# analog.net
KiCad netlist of a schematic drawn in EAGLE
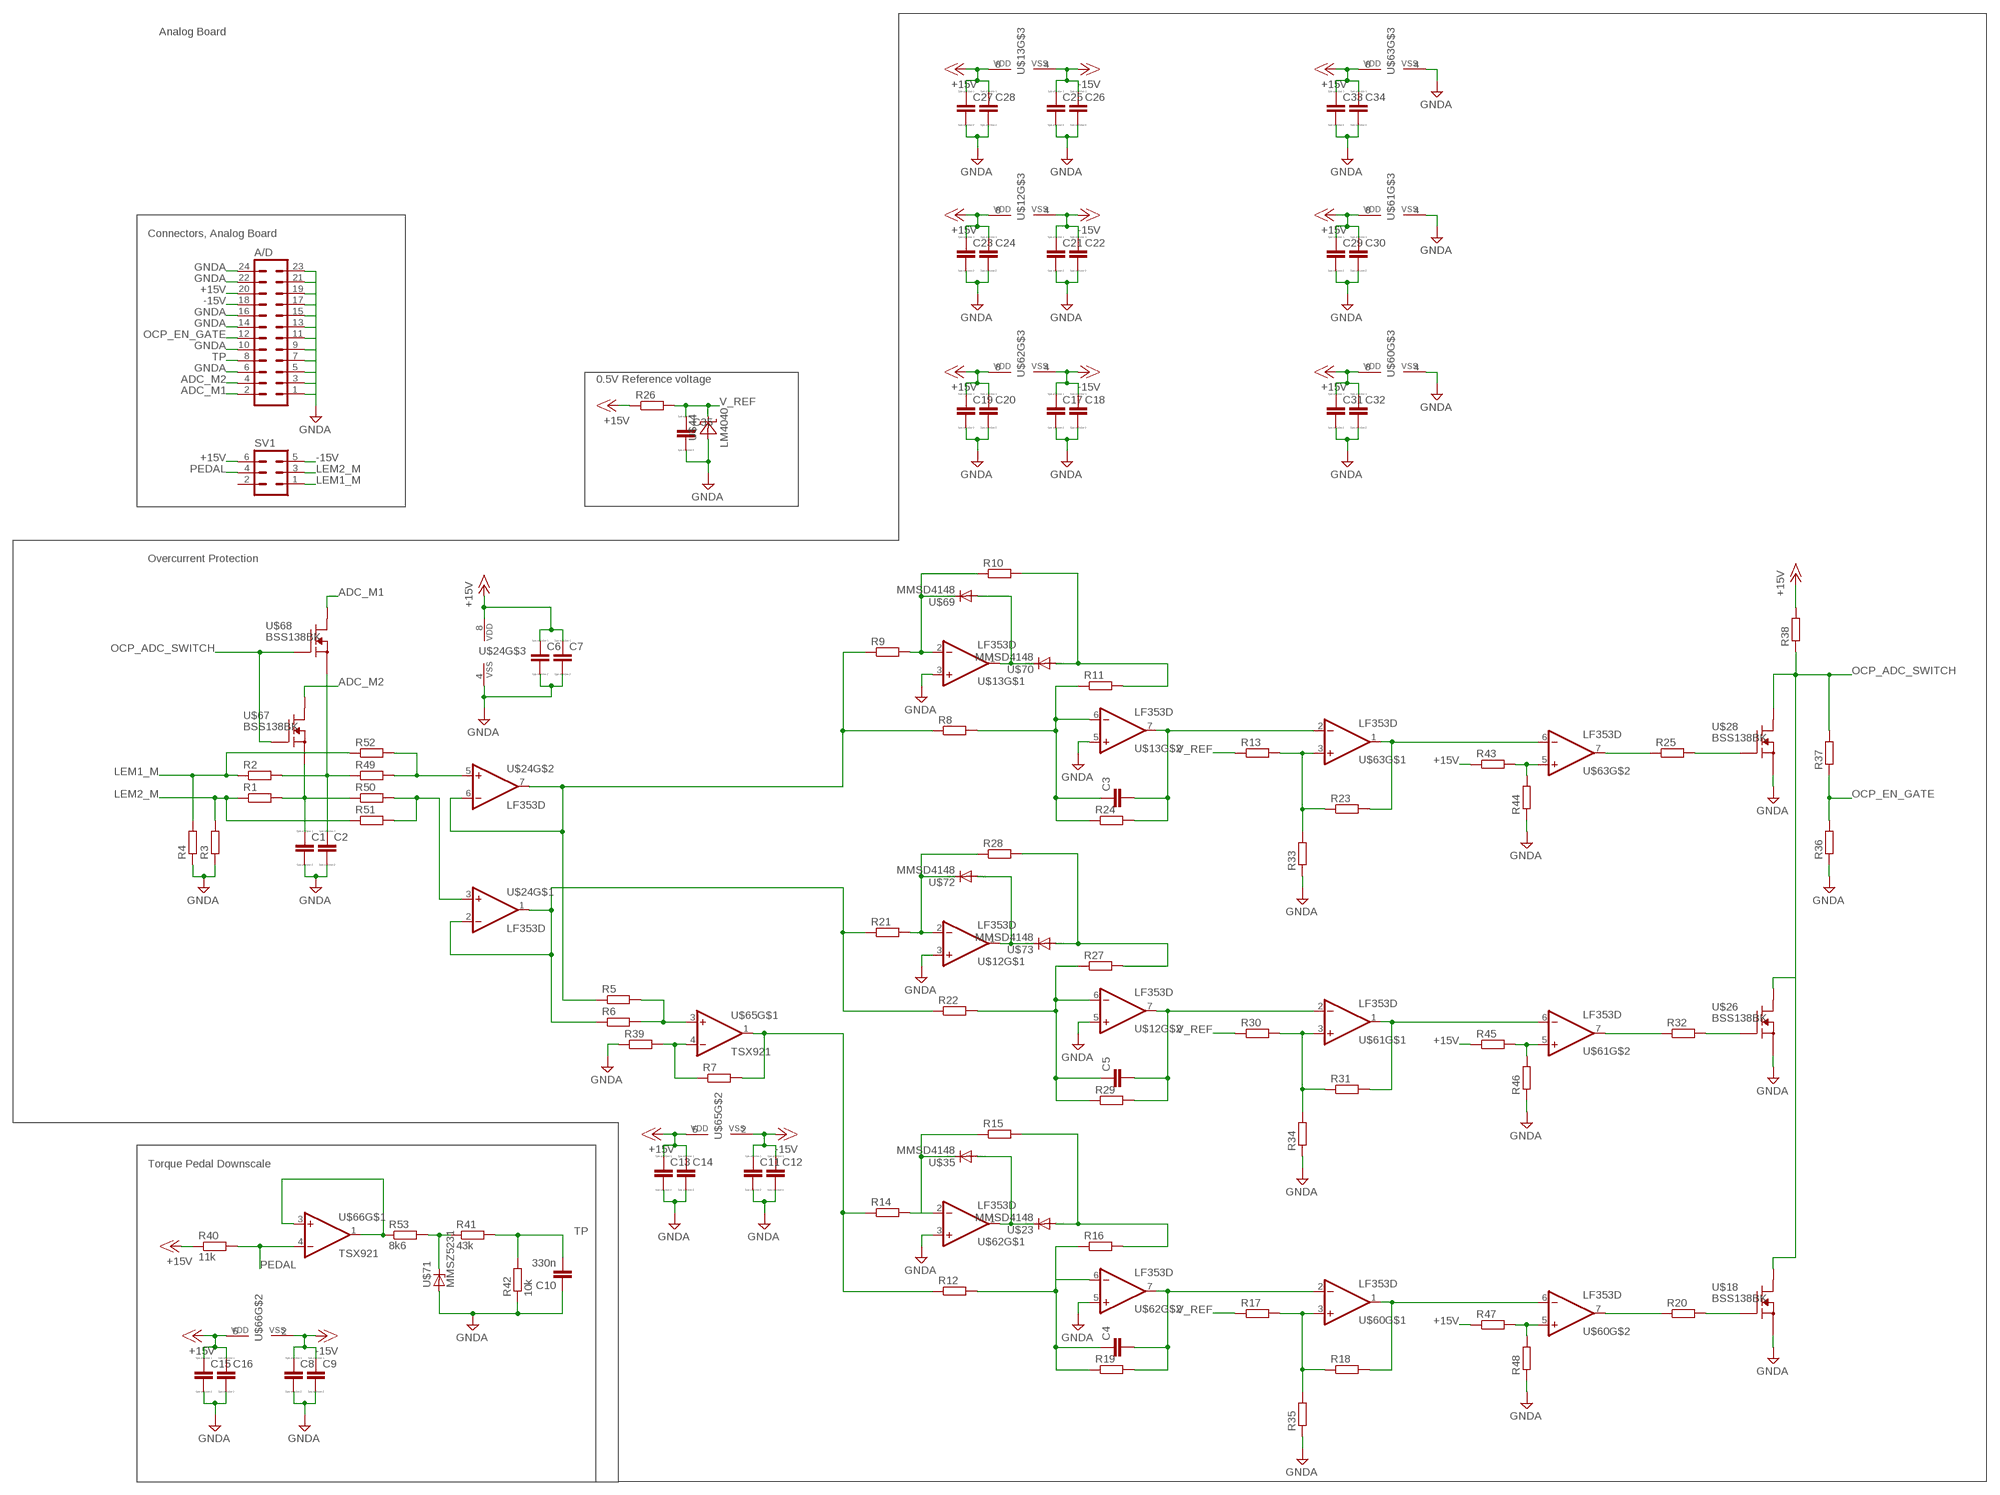
[diagram p0: schematic, sheet 1]

(export (version "E")
  (design (tool "Eeschema 10.0.6"))
  (components
    (comp (ref "A/D")
      (value "MA12-2")
      (footprint "eagle-import:MA12-2")
      (libsource (lib "eagle-import") (part "MA12-2"))
    )
    (comp (ref "C1")
      (value "CC1206")
      (footprint "eagle-import:C1206")
      (libsource (lib "eagle-import") (part "CC1206"))
    )
    (comp (ref "C2")
      (value "CC1206")
      (footprint "eagle-import:C1206")
      (libsource (lib "eagle-import") (part "CC1206"))
    )
    (comp (ref "C3")
      (value "C-EUC0805")
      (footprint "eagle-import:C0805")
      (libsource (lib "eagle-import") (part "C-EUC0805"))
    )
    (comp (ref "C4")
      (value "C-EUC0805")
      (footprint "eagle-import:C0805")
      (libsource (lib "eagle-import") (part "C-EUC0805"))
    )
    (comp (ref "C5")
      (value "C-EUC0805")
      (footprint "eagle-import:C0805")
      (libsource (lib "eagle-import") (part "C-EUC0805"))
    )
    (comp (ref "C6")
      (value "CC1206")
      (footprint "eagle-import:C1206")
      (libsource (lib "eagle-import") (part "CC1206"))
    )
    (comp (ref "C7")
      (value "CC1206")
      (footprint "eagle-import:C1206")
      (libsource (lib "eagle-import") (part "CC1206"))
    )
    (comp (ref "C8")
      (value "CC1206")
      (footprint "eagle-import:C1206")
      (libsource (lib "eagle-import") (part "CC1206"))
    )
    (comp (ref "C9")
      (value "CC1206")
      (footprint "eagle-import:C1206")
      (libsource (lib "eagle-import") (part "CC1206"))
    )
    (comp (ref "C10")
      (value "330n")
      (footprint "eagle-import:C0805")
      (libsource (lib "eagle-import") (part "C-EUC0805"))
    )
    (comp (ref "C11")
      (value "CC1206")
      (footprint "eagle-import:C1206")
      (libsource (lib "eagle-import") (part "CC1206"))
    )
    (comp (ref "C12")
      (value "CC1206")
      (footprint "eagle-import:C1206")
      (libsource (lib "eagle-import") (part "CC1206"))
    )
    (comp (ref "C13")
      (value "CC1206")
      (footprint "eagle-import:C1206")
      (libsource (lib "eagle-import") (part "CC1206"))
    )
    (comp (ref "C14")
      (value "CC1206")
      (footprint "eagle-import:C1206")
      (libsource (lib "eagle-import") (part "CC1206"))
    )
    (comp (ref "C15")
      (value "CC1206")
      (footprint "eagle-import:C1206")
      (libsource (lib "eagle-import") (part "CC1206"))
    )
    (comp (ref "C16")
      (value "CC1206")
      (footprint "eagle-import:C1206")
      (libsource (lib "eagle-import") (part "CC1206"))
    )
    (comp (ref "C17")
      (value "CC1206")
      (footprint "eagle-import:C1206")
      (libsource (lib "eagle-import") (part "CC1206"))
    )
    (comp (ref "C18")
      (value "CC1206")
      (footprint "eagle-import:C1206")
      (libsource (lib "eagle-import") (part "CC1206"))
    )
    (comp (ref "C19")
      (value "CC1206")
      (footprint "eagle-import:C1206")
      (libsource (lib "eagle-import") (part "CC1206"))
    )
    (comp (ref "C20")
      (value "CC1206")
      (footprint "eagle-import:C1206")
      (libsource (lib "eagle-import") (part "CC1206"))
    )
    (comp (ref "C21")
      (value "CC1206")
      (footprint "eagle-import:C1206")
      (libsource (lib "eagle-import") (part "CC1206"))
    )
    (comp (ref "C22")
      (value "CC1206")
      (footprint "eagle-import:C1206")
      (libsource (lib "eagle-import") (part "CC1206"))
    )
    (comp (ref "C23")
      (value "CC1206")
      (footprint "eagle-import:C1206")
      (libsource (lib "eagle-import") (part "CC1206"))
    )
    (comp (ref "C24")
      (value "CC1206")
      (footprint "eagle-import:C1206")
      (libsource (lib "eagle-import") (part "CC1206"))
    )
    (comp (ref "C25")
      (value "CC1206")
      (footprint "eagle-import:C1206")
      (libsource (lib "eagle-import") (part "CC1206"))
    )
    (comp (ref "C26")
      (value "CC1206")
      (footprint "eagle-import:C1206")
      (libsource (lib "eagle-import") (part "CC1206"))
    )
    (comp (ref "C27")
      (value "CC1206")
      (footprint "eagle-import:C1206")
      (libsource (lib "eagle-import") (part "CC1206"))
    )
    (comp (ref "C28")
      (value "CC1206")
      (footprint "eagle-import:C1206")
      (libsource (lib "eagle-import") (part "CC1206"))
    )
    (comp (ref "C29")
      (value "CC1206")
      (footprint "eagle-import:C1206")
      (libsource (lib "eagle-import") (part "CC1206"))
    )
    (comp (ref "C30")
      (value "CC1206")
      (footprint "eagle-import:C1206")
      (libsource (lib "eagle-import") (part "CC1206"))
    )
    (comp (ref "C31")
      (value "CC1206")
      (footprint "eagle-import:C1206")
      (libsource (lib "eagle-import") (part "CC1206"))
    )
    (comp (ref "C32")
      (value "CC1206")
      (footprint "eagle-import:C1206")
      (libsource (lib "eagle-import") (part "CC1206"))
    )
    (comp (ref "C33")
      (value "CC1206")
      (footprint "eagle-import:C1206")
      (libsource (lib "eagle-import") (part "CC1206"))
    )
    (comp (ref "C34")
      (value "CC1206")
      (footprint "eagle-import:C1206")
      (libsource (lib "eagle-import") (part "CC1206"))
    )
    (comp (ref "C35")
      (value "CC1206")
      (footprint "eagle-import:C1206")
      (libsource (lib "eagle-import") (part "CC1206"))
    )
    (comp (ref "R1")
      (value "R-EU_M0805")
      (footprint "eagle-import:M0805")
      (libsource (lib "eagle-import") (part "R-EU_M0805"))
    )
    (comp (ref "R2")
      (value "R-EU_M0805")
      (footprint "eagle-import:M0805")
      (libsource (lib "eagle-import") (part "R-EU_M0805"))
    )
    (comp (ref "R3")
      (value "R-EU_M0805")
      (footprint "eagle-import:M0805")
      (libsource (lib "eagle-import") (part "R-EU_M0805"))
    )
    (comp (ref "R4")
      (value "R-EU_M0805")
      (footprint "eagle-import:M0805")
      (libsource (lib "eagle-import") (part "R-EU_M0805"))
    )
    (comp (ref "R5")
      (value "R-EU_M0805")
      (footprint "eagle-import:M0805")
      (libsource (lib "eagle-import") (part "R-EU_M0805"))
    )
    (comp (ref "R6")
      (value "R-EU_M0805")
      (footprint "eagle-import:M0805")
      (libsource (lib "eagle-import") (part "R-EU_M0805"))
    )
    (comp (ref "R7")
      (value "R-EU_M0805")
      (footprint "eagle-import:M0805")
      (libsource (lib "eagle-import") (part "R-EU_M0805"))
    )
    (comp (ref "R8")
      (value "R-EU_M0805")
      (footprint "eagle-import:M0805")
      (libsource (lib "eagle-import") (part "R-EU_M0805"))
    )
    (comp (ref "R9")
      (value "R-EU_M0805")
      (footprint "eagle-import:M0805")
      (libsource (lib "eagle-import") (part "R-EU_M0805"))
    )
    (comp (ref "R10")
      (value "R-EU_M0805")
      (footprint "eagle-import:M0805")
      (libsource (lib "eagle-import") (part "R-EU_M0805"))
    )
    (comp (ref "R11")
      (value "R-EU_M0805")
      (footprint "eagle-import:M0805")
      (libsource (lib "eagle-import") (part "R-EU_M0805"))
    )
    (comp (ref "R12")
      (value "R-EU_M0805")
      (footprint "eagle-import:M0805")
      (libsource (lib "eagle-import") (part "R-EU_M0805"))
    )
    (comp (ref "R13")
      (value "R-EU_M0805")
      (footprint "eagle-import:M0805")
      (libsource (lib "eagle-import") (part "R-EU_M0805"))
    )
    (comp (ref "R14")
      (value "R-EU_M0805")
      (footprint "eagle-import:M0805")
      (libsource (lib "eagle-import") (part "R-EU_M0805"))
    )
    (comp (ref "R15")
      (value "R-EU_M0805")
      (footprint "eagle-import:M0805")
      (libsource (lib "eagle-import") (part "R-EU_M0805"))
    )
    (comp (ref "R16")
      (value "R-EU_M0805")
      (footprint "eagle-import:M0805")
      (libsource (lib "eagle-import") (part "R-EU_M0805"))
    )
    (comp (ref "R17")
      (value "R-EU_M0805")
      (footprint "eagle-import:M0805")
      (libsource (lib "eagle-import") (part "R-EU_M0805"))
    )
    (comp (ref "R18")
      (value "R-EU_M0805")
      (footprint "eagle-import:M0805")
      (libsource (lib "eagle-import") (part "R-EU_M0805"))
    )
    (comp (ref "R19")
      (value "R-EU_M0805")
      (footprint "eagle-import:M0805")
      (libsource (lib "eagle-import") (part "R-EU_M0805"))
    )
    (comp (ref "R20")
      (value "R-EU_M0805")
      (footprint "eagle-import:M0805")
      (libsource (lib "eagle-import") (part "R-EU_M0805"))
    )
    (comp (ref "R21")
      (value "R-EU_M0805")
      (footprint "eagle-import:M0805")
      (libsource (lib "eagle-import") (part "R-EU_M0805"))
    )
    (comp (ref "R22")
      (value "R-EU_M0805")
      (footprint "eagle-import:M0805")
      (libsource (lib "eagle-import") (part "R-EU_M0805"))
    )
    (comp (ref "R23")
      (value "R-EU_M0805")
      (footprint "eagle-import:M0805")
      (libsource (lib "eagle-import") (part "R-EU_M0805"))
    )
    (comp (ref "R24")
      (value "R-EU_M0805")
      (footprint "eagle-import:M0805")
      (libsource (lib "eagle-import") (part "R-EU_M0805"))
    )
    (comp (ref "R25")
      (value "R-EU_M0805")
      (footprint "eagle-import:M0805")
      (libsource (lib "eagle-import") (part "R-EU_M0805"))
    )
    (comp (ref "R26")
      (value "R-EU_M0805")
      (footprint "eagle-import:M0805")
      (libsource (lib "eagle-import") (part "R-EU_M0805"))
    )
    (comp (ref "R27")
      (value "R-EU_M0805")
      (footprint "eagle-import:M0805")
      (libsource (lib "eagle-import") (part "R-EU_M0805"))
    )
    (comp (ref "R28")
      (value "R-EU_M0805")
      (footprint "eagle-import:M0805")
      (libsource (lib "eagle-import") (part "R-EU_M0805"))
    )
    (comp (ref "R29")
      (value "R-EU_M0805")
      (footprint "eagle-import:M0805")
      (libsource (lib "eagle-import") (part "R-EU_M0805"))
    )
    (comp (ref "R30")
      (value "R-EU_M0805")
      (footprint "eagle-import:M0805")
      (libsource (lib "eagle-import") (part "R-EU_M0805"))
    )
    (comp (ref "R31")
      (value "R-EU_M0805")
      (footprint "eagle-import:M0805")
      (libsource (lib "eagle-import") (part "R-EU_M0805"))
    )
    (comp (ref "R32")
      (value "R-EU_M0805")
      (footprint "eagle-import:M0805")
      (libsource (lib "eagle-import") (part "R-EU_M0805"))
    )
    (comp (ref "R33")
      (value "R-EU_M0805")
      (footprint "eagle-import:M0805")
      (libsource (lib "eagle-import") (part "R-EU_M0805"))
    )
    (comp (ref "R34")
      (value "R-EU_M0805")
      (footprint "eagle-import:M0805")
      (libsource (lib "eagle-import") (part "R-EU_M0805"))
    )
    (comp (ref "R35")
      (value "R-EU_M0805")
      (footprint "eagle-import:M0805")
      (libsource (lib "eagle-import") (part "R-EU_M0805"))
    )
    (comp (ref "R36")
      (value "R-EU_M0805")
      (footprint "eagle-import:M0805")
      (libsource (lib "eagle-import") (part "R-EU_M0805"))
    )
    (comp (ref "R37")
      (value "R-EU_M0805")
      (footprint "eagle-import:M0805")
      (libsource (lib "eagle-import") (part "R-EU_M0805"))
    )
    (comp (ref "R38")
      (value "R-EU_M0805")
      (footprint "eagle-import:M0805")
      (libsource (lib "eagle-import") (part "R-EU_M0805"))
    )
    (comp (ref "R39")
      (value "R-EU_M0805")
      (footprint "eagle-import:M0805")
      (libsource (lib "eagle-import") (part "R-EU_M0805"))
    )
    (comp (ref "R40")
      (value "11k")
      (footprint "eagle-import:M0805")
      (libsource (lib "eagle-import") (part "R-EU_M0805"))
    )
    (comp (ref "R41")
      (value "43k")
      (footprint "eagle-import:M0805")
      (libsource (lib "eagle-import") (part "R-EU_M0805"))
    )
    (comp (ref "R42")
      (value "10k")
      (footprint "eagle-import:M0805")
      (libsource (lib "eagle-import") (part "R-EU_M0805"))
    )
    (comp (ref "R43")
      (value "R-EU_M0805")
      (footprint "eagle-import:M0805")
      (libsource (lib "eagle-import") (part "R-EU_M0805"))
    )
    (comp (ref "R44")
      (value "R-EU_M0805")
      (footprint "eagle-import:M0805")
      (libsource (lib "eagle-import") (part "R-EU_M0805"))
    )
    (comp (ref "R45")
      (value "R-EU_M0805")
      (footprint "eagle-import:M0805")
      (libsource (lib "eagle-import") (part "R-EU_M0805"))
    )
    (comp (ref "R46")
      (value "R-EU_M0805")
      (footprint "eagle-import:M0805")
      (libsource (lib "eagle-import") (part "R-EU_M0805"))
    )
    (comp (ref "R47")
      (value "R-EU_M0805")
      (footprint "eagle-import:M0805")
      (libsource (lib "eagle-import") (part "R-EU_M0805"))
    )
    (comp (ref "R48")
      (value "R-EU_M0805")
      (footprint "eagle-import:M0805")
      (libsource (lib "eagle-import") (part "R-EU_M0805"))
    )
    (comp (ref "R49")
      (value "R-EU_M0805")
      (footprint "eagle-import:M0805")
      (libsource (lib "eagle-import") (part "R-EU_M0805"))
    )
    (comp (ref "R50")
      (value "R-EU_M0805")
      (footprint "eagle-import:M0805")
      (libsource (lib "eagle-import") (part "R-EU_M0805"))
    )
    (comp (ref "R51")
      (value "R-EU_M0805")
      (footprint "eagle-import:M0805")
      (libsource (lib "eagle-import") (part "R-EU_M0805"))
    )
    (comp (ref "R52")
      (value "R-EU_M0805")
      (footprint "eagle-import:M0805")
      (libsource (lib "eagle-import") (part "R-EU_M0805"))
    )
    (comp (ref "R53")
      (value "8k6")
      (footprint "eagle-import:M0805")
      (libsource (lib "eagle-import") (part "R-EU_M0805"))
    )
    (comp (ref "SV1")
      (value "MA03-2")
      (footprint "eagle-import:MA03-2")
      (libsource (lib "eagle-import") (part "MA03-2"))
    )
    (comp (ref "U$12")
      (value "LF353D")
      (footprint "eagle-import:SO08")
      (libsource (lib "eagle-import") (part "LF353D"))
    )
    (comp (ref "U$13")
      (value "LF353D")
      (footprint "eagle-import:SO08")
      (libsource (lib "eagle-import") (part "LF353D"))
    )
    (comp (ref "U$18")
      (value "BSS138BK")
      (footprint "eagle-import:SOT23")
      (libsource (lib "eagle-import") (part "BSS138BK"))
    )
    (comp (ref "U$23")
      (value "MMSD4148")
      (footprint "eagle-import:SOD123")
      (libsource (lib "eagle-import") (part "MMSD4148"))
    )
    (comp (ref "U$24")
      (value "LF353D")
      (footprint "eagle-import:SO08")
      (libsource (lib "eagle-import") (part "LF353D"))
    )
    (comp (ref "U$26")
      (value "BSS138BK")
      (footprint "eagle-import:SOT23")
      (libsource (lib "eagle-import") (part "BSS138BK"))
    )
    (comp (ref "U$28")
      (value "BSS138BK")
      (footprint "eagle-import:SOT23")
      (libsource (lib "eagle-import") (part "BSS138BK"))
    )
    (comp (ref "U$35")
      (value "MMSD4148")
      (footprint "eagle-import:SOD123")
      (libsource (lib "eagle-import") (part "MMSD4148"))
    )
    (comp (ref "U$44")
      (value "LM4040")
      (footprint "eagle-import:SOT23")
      (libsource (lib "eagle-import") (part "LM4040"))
    )
    (comp (ref "U$60")
      (value "LF353D")
      (footprint "eagle-import:SO08")
      (libsource (lib "eagle-import") (part "LF353D"))
    )
    (comp (ref "U$61")
      (value "LF353D")
      (footprint "eagle-import:SO08")
      (libsource (lib "eagle-import") (part "LF353D"))
    )
    (comp (ref "U$62")
      (value "LF353D")
      (footprint "eagle-import:SO08")
      (libsource (lib "eagle-import") (part "LF353D"))
    )
    (comp (ref "U$63")
      (value "LF353D")
      (footprint "eagle-import:SO08")
      (libsource (lib "eagle-import") (part "LF353D"))
    )
    (comp (ref "U$65")
      (value "TSX921")
      (footprint "eagle-import:SOT23-5")
      (libsource (lib "eagle-import") (part "TSX921"))
    )
    (comp (ref "U$66")
      (value "TSX921")
      (footprint "eagle-import:SOT23-5")
      (libsource (lib "eagle-import") (part "TSX921"))
    )
    (comp (ref "U$67")
      (value "BSS138BK")
      (footprint "eagle-import:SOT23")
      (libsource (lib "eagle-import") (part "BSS138BK"))
    )
    (comp (ref "U$68")
      (value "BSS138BK")
      (footprint "eagle-import:SOT23")
      (libsource (lib "eagle-import") (part "BSS138BK"))
    )
    (comp (ref "U$69")
      (value "MMSD4148")
      (footprint "eagle-import:SOD123")
      (libsource (lib "eagle-import") (part "MMSD4148"))
    )
    (comp (ref "U$70")
      (value "MMSD4148")
      (footprint "eagle-import:SOD123")
      (libsource (lib "eagle-import") (part "MMSD4148"))
    )
    (comp (ref "U$71")
      (value "MMSZ5231")
      (footprint "eagle-import:SOD123")
      (libsource (lib "eagle-import") (part "MMSZ5231"))
    )
    (comp (ref "U$72")
      (value "MMSD4148")
      (footprint "eagle-import:SOD123")
      (libsource (lib "eagle-import") (part "MMSD4148"))
    )
    (comp (ref "U$73")
      (value "MMSD4148")
      (footprint "eagle-import:SOD123")
      (libsource (lib "eagle-import") (part "MMSD4148"))
    )
  )
  (nets
    (net (code "1") (name "+15V") (class "Default")
      (node (ref "A/D") (pin "20") (pinfunction "20_20") (pintype "passive"))
      (node (ref "C13") (pin "1") (pinfunction "1_1") (pintype "passive"))
      (node (ref "C14") (pin "1") (pinfunction "1_1") (pintype "passive"))
      (node (ref "C15") (pin "1") (pinfunction "1_1") (pintype "passive"))
      (node (ref "C16") (pin "1") (pinfunction "1_1") (pintype "passive"))
      (node (ref "C19") (pin "1") (pinfunction "1_1") (pintype "passive"))
      (node (ref "C20") (pin "1") (pinfunction "1_1") (pintype "passive"))
      (node (ref "C23") (pin "1") (pinfunction "1_1") (pintype "passive"))
      (node (ref "C24") (pin "1") (pinfunction "1_1") (pintype "passive"))
      (node (ref "C27") (pin "1") (pinfunction "1_1") (pintype "passive"))
      (node (ref "C28") (pin "1") (pinfunction "1_1") (pintype "passive"))
      (node (ref "C29") (pin "1") (pinfunction "1_1") (pintype "passive"))
      (node (ref "C30") (pin "1") (pinfunction "1_1") (pintype "passive"))
      (node (ref "C31") (pin "1") (pinfunction "1_1") (pintype "passive"))
      (node (ref "C32") (pin "1") (pinfunction "1_1") (pintype "passive"))
      (node (ref "C33") (pin "1") (pinfunction "1_1") (pintype "passive"))
      (node (ref "C34") (pin "1") (pinfunction "1_1") (pintype "passive"))
      (node (ref "C6") (pin "1") (pinfunction "1_1") (pintype "passive"))
      (node (ref "C7") (pin "1") (pinfunction "1_1") (pintype "passive"))
      (node (ref "R26") (pin "1") (pinfunction "1_1") (pintype "passive"))
      (node (ref "R38") (pin "2") (pinfunction "2_2") (pintype "passive"))
      (node (ref "R40") (pin "1") (pinfunction "1_1") (pintype "passive"))
      (node (ref "R43") (pin "1") (pinfunction "1_1") (pintype "passive"))
      (node (ref "R45") (pin "1") (pinfunction "1_1") (pintype "passive"))
      (node (ref "R47") (pin "1") (pinfunction "1_1") (pintype "passive"))
      (node (ref "SV1") (pin "6") (pinfunction "6_6") (pintype "passive"))
      (node (ref "U$12") (pin "8") (pinfunction "VDD_8") (pintype "power_in"))
      (node (ref "U$13") (pin "8") (pinfunction "VDD_8") (pintype "power_in"))
      (node (ref "U$24") (pin "8") (pinfunction "VDD_8") (pintype "power_in"))
      (node (ref "U$60") (pin "8") (pinfunction "VDD_8") (pintype "power_in"))
      (node (ref "U$61") (pin "8") (pinfunction "VDD_8") (pintype "power_in"))
      (node (ref "U$62") (pin "8") (pinfunction "VDD_8") (pintype "power_in"))
      (node (ref "U$63") (pin "8") (pinfunction "VDD_8") (pintype "power_in"))
      (node (ref "U$65") (pin "5") (pinfunction "VDD_5") (pintype "power_in"))
      (node (ref "U$66") (pin "5") (pinfunction "VDD_5") (pintype "power_in"))
    )
    (net (code "2") (name "-15V") (class "Default")
      (node (ref "A/D") (pin "18") (pinfunction "18_18") (pintype "passive"))
      (node (ref "C11") (pin "1") (pinfunction "1_1") (pintype "passive"))
      (node (ref "C12") (pin "1") (pinfunction "1_1") (pintype "passive"))
      (node (ref "C17") (pin "1") (pinfunction "1_1") (pintype "passive"))
      (node (ref "C18") (pin "1") (pinfunction "1_1") (pintype "passive"))
      (node (ref "C21") (pin "1") (pinfunction "1_1") (pintype "passive"))
      (node (ref "C22") (pin "1") (pinfunction "1_1") (pintype "passive"))
      (node (ref "C25") (pin "1") (pinfunction "1_1") (pintype "passive"))
      (node (ref "C26") (pin "1") (pinfunction "1_1") (pintype "passive"))
      (node (ref "C8") (pin "1") (pinfunction "1_1") (pintype "passive"))
      (node (ref "C9") (pin "1") (pinfunction "1_1") (pintype "passive"))
      (node (ref "SV1") (pin "5") (pinfunction "5_5") (pintype "passive"))
      (node (ref "U$12") (pin "4") (pinfunction "VSS_4") (pintype "power_in"))
      (node (ref "U$13") (pin "4") (pinfunction "VSS_4") (pintype "power_in"))
      (node (ref "U$62") (pin "4") (pinfunction "VSS_4") (pintype "power_in"))
      (node (ref "U$65") (pin "2") (pinfunction "VSS_2") (pintype "power_in"))
      (node (ref "U$66") (pin "2") (pinfunction "VSS_2") (pintype "power_in"))
    )
    (net (code "3") (name "/ADC_M1") (class "Default")
      (node (ref "A/D") (pin "2") (pinfunction "2_2") (pintype "passive"))
      (node (ref "U$68") (pin "3") (pinfunction "D_3") (pintype "passive"))
    )
    (net (code "4") (name "/ADC_M2") (class "Default")
      (node (ref "A/D") (pin "4") (pinfunction "4_4") (pintype "passive"))
      (node (ref "U$67") (pin "3") (pinfunction "D_3") (pintype "passive"))
    )
    (net (code "5") (name "/LEM1_M") (class "Default")
      (node (ref "R2") (pin "1") (pinfunction "1_1") (pintype "passive"))
      (node (ref "R4") (pin "2") (pinfunction "2_2") (pintype "passive"))
      (node (ref "R52") (pin "1") (pinfunction "1_1") (pintype "passive"))
      (node (ref "SV1") (pin "1") (pinfunction "1_1") (pintype "passive"))
    )
    (net (code "6") (name "/LEM2_M") (class "Default")
      (node (ref "R1") (pin "1") (pinfunction "1_1") (pintype "passive"))
      (node (ref "R3") (pin "2") (pinfunction "2_2") (pintype "passive"))
      (node (ref "R51") (pin "1") (pinfunction "1_1") (pintype "passive"))
      (node (ref "SV1") (pin "3") (pinfunction "3_3") (pintype "passive"))
    )
    (net (code "7") (name "/OCP_ADC_SWITCH") (class "Default")
      (node (ref "R37") (pin "2") (pinfunction "2_2") (pintype "passive"))
      (node (ref "R38") (pin "1") (pinfunction "1_1") (pintype "passive"))
      (node (ref "U$18") (pin "3") (pinfunction "D_3") (pintype "passive"))
      (node (ref "U$26") (pin "3") (pinfunction "D_3") (pintype "passive"))
      (node (ref "U$28") (pin "3") (pinfunction "D_3") (pintype "passive"))
      (node (ref "U$67") (pin "1") (pinfunction "G_1") (pintype "passive"))
      (node (ref "U$68") (pin "1") (pinfunction "G_1") (pintype "passive"))
    )
    (net (code "8") (name "/OCP_EN_GATE") (class "Default")
      (node (ref "A/D") (pin "12") (pinfunction "12_12") (pintype "passive"))
      (node (ref "R36") (pin "2") (pinfunction "2_2") (pintype "passive"))
      (node (ref "R37") (pin "1") (pinfunction "1_1") (pintype "passive"))
    )
    (net (code "9") (name "/PEDAL") (class "Default")
      (node (ref "R40") (pin "2") (pinfunction "2_2") (pintype "passive"))
      (node (ref "SV1") (pin "4") (pinfunction "4_4") (pintype "passive"))
      (node (ref "U$66") (pin "4") (pinfunction "-IN_4") (pintype "input"))
    )
    (net (code "10") (name "/TP") (class "Default")
      (node (ref "A/D") (pin "8") (pinfunction "8_8") (pintype "passive"))
      (node (ref "C10") (pin "2") (pinfunction "2_2") (pintype "passive"))
      (node (ref "R41") (pin "2") (pinfunction "2_2") (pintype "passive"))
      (node (ref "R42") (pin "2") (pinfunction "2_2") (pintype "passive"))
    )
    (net (code "11") (name "/V_REF") (class "Default")
      (node (ref "C35") (pin "1") (pinfunction "1_1") (pintype "passive"))
      (node (ref "R13") (pin "1") (pinfunction "1_1") (pintype "passive"))
      (node (ref "R17") (pin "1") (pinfunction "1_1") (pintype "passive"))
      (node (ref "R26") (pin "2") (pinfunction "2_2") (pintype "passive"))
      (node (ref "R30") (pin "1") (pinfunction "1_1") (pintype "passive"))
      (node (ref "U$44") (pin "2") (pinfunction "C_2") (pintype "passive"))
    )
    (net (code "12") (name "GNDA") (class "Default")
      (node (ref "A/D") (pin "1") (pinfunction "1_1") (pintype "passive"))
      (node (ref "A/D") (pin "10") (pinfunction "10_10") (pintype "passive"))
      (node (ref "A/D") (pin "11") (pinfunction "11_11") (pintype "passive"))
      (node (ref "A/D") (pin "13") (pinfunction "13_13") (pintype "passive"))
      (node (ref "A/D") (pin "14") (pinfunction "14_14") (pintype "passive"))
      (node (ref "A/D") (pin "15") (pinfunction "15_15") (pintype "passive"))
      (node (ref "A/D") (pin "16") (pinfunction "16_16") (pintype "passive"))
      (node (ref "A/D") (pin "22") (pinfunction "22_22") (pintype "passive"))
      (node (ref "A/D") (pin "23") (pinfunction "23_23") (pintype "passive"))
      (node (ref "A/D") (pin "24") (pinfunction "24_24") (pintype "passive"))
      (node (ref "A/D") (pin "3") (pinfunction "3_3") (pintype "passive"))
      (node (ref "A/D") (pin "5") (pinfunction "5_5") (pintype "passive"))
      (node (ref "A/D") (pin "6") (pinfunction "6_6") (pintype "passive"))
      (node (ref "A/D") (pin "7") (pinfunction "7_7") (pintype "passive"))
      (node (ref "A/D") (pin "9") (pinfunction "9_9") (pintype "passive"))
      (node (ref "C1") (pin "2") (pinfunction "2_2") (pintype "passive"))
      (node (ref "C10") (pin "1") (pinfunction "1_1") (pintype "passive"))
      (node (ref "C11") (pin "2") (pinfunction "2_2") (pintype "passive"))
      (node (ref "C12") (pin "2") (pinfunction "2_2") (pintype "passive"))
      (node (ref "C13") (pin "2") (pinfunction "2_2") (pintype "passive"))
      (node (ref "C14") (pin "2") (pinfunction "2_2") (pintype "passive"))
      (node (ref "C15") (pin "2") (pinfunction "2_2") (pintype "passive"))
      (node (ref "C16") (pin "2") (pinfunction "2_2") (pintype "passive"))
      (node (ref "C17") (pin "2") (pinfunction "2_2") (pintype "passive"))
      (node (ref "C18") (pin "2") (pinfunction "2_2") (pintype "passive"))
      (node (ref "C19") (pin "2") (pinfunction "2_2") (pintype "passive"))
      (node (ref "C2") (pin "2") (pinfunction "2_2") (pintype "passive"))
      (node (ref "C20") (pin "2") (pinfunction "2_2") (pintype "passive"))
      (node (ref "C21") (pin "2") (pinfunction "2_2") (pintype "passive"))
      (node (ref "C22") (pin "2") (pinfunction "2_2") (pintype "passive"))
      (node (ref "C23") (pin "2") (pinfunction "2_2") (pintype "passive"))
      (node (ref "C24") (pin "2") (pinfunction "2_2") (pintype "passive"))
      (node (ref "C25") (pin "2") (pinfunction "2_2") (pintype "passive"))
      (node (ref "C26") (pin "2") (pinfunction "2_2") (pintype "passive"))
      (node (ref "C27") (pin "2") (pinfunction "2_2") (pintype "passive"))
      (node (ref "C28") (pin "2") (pinfunction "2_2") (pintype "passive"))
      (node (ref "C29") (pin "2") (pinfunction "2_2") (pintype "passive"))
      (node (ref "C30") (pin "2") (pinfunction "2_2") (pintype "passive"))
      (node (ref "C31") (pin "2") (pinfunction "2_2") (pintype "passive"))
      (node (ref "C32") (pin "2") (pinfunction "2_2") (pintype "passive"))
      (node (ref "C33") (pin "2") (pinfunction "2_2") (pintype "passive"))
      (node (ref "C34") (pin "2") (pinfunction "2_2") (pintype "passive"))
      (node (ref "C35") (pin "2") (pinfunction "2_2") (pintype "passive"))
      (node (ref "C6") (pin "2") (pinfunction "2_2") (pintype "passive"))
      (node (ref "C7") (pin "2") (pinfunction "2_2") (pintype "passive"))
      (node (ref "C8") (pin "2") (pinfunction "2_2") (pintype "passive"))
      (node (ref "C9") (pin "2") (pinfunction "2_2") (pintype "passive"))
      (node (ref "R3") (pin "1") (pinfunction "1_1") (pintype "passive"))
      (node (ref "R33") (pin "1") (pinfunction "1_1") (pintype "passive"))
      (node (ref "R34") (pin "1") (pinfunction "1_1") (pintype "passive"))
      (node (ref "R35") (pin "1") (pinfunction "1_1") (pintype "passive"))
      (node (ref "R36") (pin "1") (pinfunction "1_1") (pintype "passive"))
      (node (ref "R39") (pin "1") (pinfunction "1_1") (pintype "passive"))
      (node (ref "R4") (pin "1") (pinfunction "1_1") (pintype "passive"))
      (node (ref "R42") (pin "1") (pinfunction "1_1") (pintype "passive"))
      (node (ref "R44") (pin "1") (pinfunction "1_1") (pintype "passive"))
      (node (ref "R46") (pin "1") (pinfunction "1_1") (pintype "passive"))
      (node (ref "R48") (pin "1") (pinfunction "1_1") (pintype "passive"))
      (node (ref "U$12") (pin "3") (pinfunction "+IN_3") (pintype "input"))
      (node (ref "U$12") (pin "5") (pinfunction "+IN_5") (pintype "input"))
      (node (ref "U$13") (pin "3") (pinfunction "+IN_3") (pintype "input"))
      (node (ref "U$13") (pin "5") (pinfunction "+IN_5") (pintype "input"))
      (node (ref "U$18") (pin "2") (pinfunction "S_2") (pintype "passive"))
      (node (ref "U$24") (pin "4") (pinfunction "VSS_4") (pintype "power_in"))
      (node (ref "U$26") (pin "2") (pinfunction "S_2") (pintype "passive"))
      (node (ref "U$28") (pin "2") (pinfunction "S_2") (pintype "passive"))
      (node (ref "U$44") (pin "1") (pinfunction "A_1") (pintype "passive"))
      (node (ref "U$60") (pin "4") (pinfunction "VSS_4") (pintype "power_in"))
      (node (ref "U$61") (pin "4") (pinfunction "VSS_4") (pintype "power_in"))
      (node (ref "U$62") (pin "3") (pinfunction "+IN_3") (pintype "input"))
      (node (ref "U$62") (pin "5") (pinfunction "+IN_5") (pintype "input"))
      (node (ref "U$63") (pin "4") (pinfunction "VSS_4") (pintype "power_in"))
      (node (ref "U$71") (pin "A") (pinfunction "A_A") (pintype "passive"))
    )
    (net (code "13") (name "Net-(R10-Pad2)") (class "Default")
      (node (ref "R10") (pin "2") (pinfunction "2_2") (pintype "passive"))
      (node (ref "R11") (pin "2") (pinfunction "2_2") (pintype "passive"))
      (node (ref "U$70") (pin "A") (pinfunction "A_A") (pintype "passive"))
    )
    (net (code "14") (name "Net-(R15-Pad2)") (class "Default")
      (node (ref "R15") (pin "2") (pinfunction "2_2") (pintype "passive"))
      (node (ref "R16") (pin "2") (pinfunction "2_2") (pintype "passive"))
      (node (ref "U$23") (pin "A") (pinfunction "A_A") (pintype "passive"))
    )
    (net (code "15") (name "Net-(R27-Pad2)") (class "Default")
      (node (ref "R27") (pin "2") (pinfunction "2_2") (pintype "passive"))
      (node (ref "R28") (pin "2") (pinfunction "2_2") (pintype "passive"))
      (node (ref "U$73") (pin "A") (pinfunction "A_A") (pintype "passive"))
    )
    (net (code "16") (name "Net-(R41-Pad1)") (class "Default")
      (node (ref "R41") (pin "1") (pinfunction "1_1") (pintype "passive"))
      (node (ref "R53") (pin "2") (pinfunction "2_2") (pintype "passive"))
      (node (ref "U$71") (pin "C") (pinfunction "C_C") (pintype "passive"))
    )
    (net (code "17") (name "Net-(U$12A--IN)") (class "Default")
      (node (ref "R21") (pin "2") (pinfunction "2_2") (pintype "passive"))
      (node (ref "R28") (pin "1") (pinfunction "1_1") (pintype "passive"))
      (node (ref "U$12") (pin "2") (pinfunction "-IN_2") (pintype "input"))
      (node (ref "U$72") (pin "C") (pinfunction "C_C") (pintype "passive"))
    )
    (net (code "18") (name "Net-(U$12A-OUT)") (class "Default")
      (node (ref "U$12") (pin "1") (pinfunction "OUT_1") (pintype "output"))
      (node (ref "U$72") (pin "A") (pinfunction "A_A") (pintype "passive"))
      (node (ref "U$73") (pin "C") (pinfunction "C_C") (pintype "passive"))
    )
    (net (code "19") (name "Net-(U$12B--IN)") (class "Default")
      (node (ref "C5") (pin "1") (pinfunction "1_1") (pintype "passive"))
      (node (ref "R22") (pin "2") (pinfunction "2_2") (pintype "passive"))
      (node (ref "R27") (pin "1") (pinfunction "1_1") (pintype "passive"))
      (node (ref "R29") (pin "1") (pinfunction "1_1") (pintype "passive"))
      (node (ref "U$12") (pin "6") (pinfunction "-IN_6") (pintype "input"))
    )
    (net (code "20") (name "Net-(U$12B-OUT)") (class "Default")
      (node (ref "C5") (pin "2") (pinfunction "2_2") (pintype "passive"))
      (node (ref "R29") (pin "2") (pinfunction "2_2") (pintype "passive"))
      (node (ref "U$12") (pin "7") (pinfunction "OUT_7") (pintype "output"))
      (node (ref "U$61") (pin "2") (pinfunction "-IN_2") (pintype "input"))
    )
    (net (code "21") (name "Net-(U$13A--IN)") (class "Default")
      (node (ref "R10") (pin "1") (pinfunction "1_1") (pintype "passive"))
      (node (ref "R9") (pin "2") (pinfunction "2_2") (pintype "passive"))
      (node (ref "U$13") (pin "2") (pinfunction "-IN_2") (pintype "input"))
      (node (ref "U$69") (pin "C") (pinfunction "C_C") (pintype "passive"))
    )
    (net (code "22") (name "Net-(U$13A-OUT)") (class "Default")
      (node (ref "U$13") (pin "1") (pinfunction "OUT_1") (pintype "output"))
      (node (ref "U$69") (pin "A") (pinfunction "A_A") (pintype "passive"))
      (node (ref "U$70") (pin "C") (pinfunction "C_C") (pintype "passive"))
    )
    (net (code "23") (name "Net-(U$13B--IN)") (class "Default")
      (node (ref "C3") (pin "1") (pinfunction "1_1") (pintype "passive"))
      (node (ref "R11") (pin "1") (pinfunction "1_1") (pintype "passive"))
      (node (ref "R24") (pin "1") (pinfunction "1_1") (pintype "passive"))
      (node (ref "R8") (pin "2") (pinfunction "2_2") (pintype "passive"))
      (node (ref "U$13") (pin "6") (pinfunction "-IN_6") (pintype "input"))
    )
    (net (code "24") (name "Net-(U$13B-OUT)") (class "Default")
      (node (ref "C3") (pin "2") (pinfunction "2_2") (pintype "passive"))
      (node (ref "R24") (pin "2") (pinfunction "2_2") (pintype "passive"))
      (node (ref "U$13") (pin "7") (pinfunction "OUT_7") (pintype "output"))
      (node (ref "U$63") (pin "2") (pinfunction "-IN_2") (pintype "input"))
    )
    (net (code "25") (name "Net-(U$18-G)") (class "Default")
      (node (ref "R20") (pin "2") (pinfunction "2_2") (pintype "passive"))
      (node (ref "U$18") (pin "1") (pinfunction "G_1") (pintype "passive"))
    )
    (net (code "26") (name "Net-(U$24A-+IN)") (class "Default")
      (node (ref "R50") (pin "2") (pinfunction "2_2") (pintype "passive"))
      (node (ref "R51") (pin "2") (pinfunction "2_2") (pintype "passive"))
      (node (ref "U$24") (pin "3") (pinfunction "+IN_3") (pintype "input"))
    )
    (net (code "27") (name "Net-(U$24A--IN)") (class "Default")
      (node (ref "R21") (pin "1") (pinfunction "1_1") (pintype "passive"))
      (node (ref "R22") (pin "1") (pinfunction "1_1") (pintype "passive"))
      (node (ref "R6") (pin "1") (pinfunction "1_1") (pintype "passive"))
      (node (ref "U$24") (pin "1") (pinfunction "OUT_1") (pintype "output"))
      (node (ref "U$24") (pin "2") (pinfunction "-IN_2") (pintype "input"))
    )
    (net (code "28") (name "Net-(U$24B-+IN)") (class "Default")
      (node (ref "R49") (pin "2") (pinfunction "2_2") (pintype "passive"))
      (node (ref "R52") (pin "2") (pinfunction "2_2") (pintype "passive"))
      (node (ref "U$24") (pin "5") (pinfunction "+IN_5") (pintype "input"))
    )
    (net (code "29") (name "Net-(U$24B--IN)") (class "Default")
      (node (ref "R5") (pin "1") (pinfunction "1_1") (pintype "passive"))
      (node (ref "R8") (pin "1") (pinfunction "1_1") (pintype "passive"))
      (node (ref "R9") (pin "1") (pinfunction "1_1") (pintype "passive"))
      (node (ref "U$24") (pin "6") (pinfunction "-IN_6") (pintype "input"))
      (node (ref "U$24") (pin "7") (pinfunction "OUT_7") (pintype "output"))
    )
    (net (code "30") (name "Net-(U$26-G)") (class "Default")
      (node (ref "R32") (pin "2") (pinfunction "2_2") (pintype "passive"))
      (node (ref "U$26") (pin "1") (pinfunction "G_1") (pintype "passive"))
    )
    (net (code "31") (name "Net-(U$28-G)") (class "Default")
      (node (ref "R25") (pin "2") (pinfunction "2_2") (pintype "passive"))
      (node (ref "U$28") (pin "1") (pinfunction "G_1") (pintype "passive"))
    )
    (net (code "32") (name "Net-(U$60A-+IN)") (class "Default")
      (node (ref "R17") (pin "2") (pinfunction "2_2") (pintype "passive"))
      (node (ref "R18") (pin "1") (pinfunction "1_1") (pintype "passive"))
      (node (ref "R35") (pin "2") (pinfunction "2_2") (pintype "passive"))
      (node (ref "U$60") (pin "3") (pinfunction "+IN_3") (pintype "input"))
    )
    (net (code "33") (name "Net-(U$60A--IN)") (class "Default")
      (node (ref "C4") (pin "2") (pinfunction "2_2") (pintype "passive"))
      (node (ref "R19") (pin "2") (pinfunction "2_2") (pintype "passive"))
      (node (ref "U$60") (pin "2") (pinfunction "-IN_2") (pintype "input"))
      (node (ref "U$62") (pin "7") (pinfunction "OUT_7") (pintype "output"))
    )
    (net (code "34") (name "Net-(U$60A-OUT)") (class "Default")
      (node (ref "R18") (pin "2") (pinfunction "2_2") (pintype "passive"))
      (node (ref "U$60") (pin "1") (pinfunction "OUT_1") (pintype "output"))
      (node (ref "U$60") (pin "6") (pinfunction "-IN_6") (pintype "input"))
    )
    (net (code "35") (name "Net-(U$60B-+IN)") (class "Default")
      (node (ref "R47") (pin "2") (pinfunction "2_2") (pintype "passive"))
      (node (ref "R48") (pin "2") (pinfunction "2_2") (pintype "passive"))
      (node (ref "U$60") (pin "5") (pinfunction "+IN_5") (pintype "input"))
    )
    (net (code "36") (name "Net-(U$60B-OUT)") (class "Default")
      (node (ref "R20") (pin "1") (pinfunction "1_1") (pintype "passive"))
      (node (ref "U$60") (pin "7") (pinfunction "OUT_7") (pintype "output"))
    )
    (net (code "37") (name "Net-(U$61A-+IN)") (class "Default")
      (node (ref "R30") (pin "2") (pinfunction "2_2") (pintype "passive"))
      (node (ref "R31") (pin "1") (pinfunction "1_1") (pintype "passive"))
      (node (ref "R34") (pin "2") (pinfunction "2_2") (pintype "passive"))
      (node (ref "U$61") (pin "3") (pinfunction "+IN_3") (pintype "input"))
    )
    (net (code "38") (name "Net-(U$61A-OUT)") (class "Default")
      (node (ref "R31") (pin "2") (pinfunction "2_2") (pintype "passive"))
      (node (ref "U$61") (pin "1") (pinfunction "OUT_1") (pintype "output"))
      (node (ref "U$61") (pin "6") (pinfunction "-IN_6") (pintype "input"))
    )
    (net (code "39") (name "Net-(U$61B-+IN)") (class "Default")
      (node (ref "R45") (pin "2") (pinfunction "2_2") (pintype "passive"))
      (node (ref "R46") (pin "2") (pinfunction "2_2") (pintype "passive"))
      (node (ref "U$61") (pin "5") (pinfunction "+IN_5") (pintype "input"))
    )
    (net (code "40") (name "Net-(U$61B-OUT)") (class "Default")
      (node (ref "R32") (pin "1") (pinfunction "1_1") (pintype "passive"))
      (node (ref "U$61") (pin "7") (pinfunction "OUT_7") (pintype "output"))
    )
    (net (code "41") (name "Net-(U$62A--IN)") (class "Default")
      (node (ref "R14") (pin "2") (pinfunction "2_2") (pintype "passive"))
      (node (ref "R15") (pin "1") (pinfunction "1_1") (pintype "passive"))
      (node (ref "U$35") (pin "C") (pinfunction "C_C") (pintype "passive"))
      (node (ref "U$62") (pin "2") (pinfunction "-IN_2") (pintype "input"))
    )
    (net (code "42") (name "Net-(U$62A-OUT)") (class "Default")
      (node (ref "U$23") (pin "C") (pinfunction "C_C") (pintype "passive"))
      (node (ref "U$35") (pin "A") (pinfunction "A_A") (pintype "passive"))
      (node (ref "U$62") (pin "1") (pinfunction "OUT_1") (pintype "output"))
    )
    (net (code "43") (name "Net-(U$62B--IN)") (class "Default")
      (node (ref "C4") (pin "1") (pinfunction "1_1") (pintype "passive"))
      (node (ref "R12") (pin "2") (pinfunction "2_2") (pintype "passive"))
      (node (ref "R16") (pin "1") (pinfunction "1_1") (pintype "passive"))
      (node (ref "R19") (pin "1") (pinfunction "1_1") (pintype "passive"))
      (node (ref "U$62") (pin "6") (pinfunction "-IN_6") (pintype "input"))
    )
    (net (code "44") (name "Net-(U$63A-+IN)") (class "Default")
      (node (ref "R13") (pin "2") (pinfunction "2_2") (pintype "passive"))
      (node (ref "R23") (pin "1") (pinfunction "1_1") (pintype "passive"))
      (node (ref "R33") (pin "2") (pinfunction "2_2") (pintype "passive"))
      (node (ref "U$63") (pin "3") (pinfunction "+IN_3") (pintype "input"))
    )
    (net (code "45") (name "Net-(U$63A-OUT)") (class "Default")
      (node (ref "R23") (pin "2") (pinfunction "2_2") (pintype "passive"))
      (node (ref "U$63") (pin "1") (pinfunction "OUT_1") (pintype "output"))
      (node (ref "U$63") (pin "6") (pinfunction "-IN_6") (pintype "input"))
    )
    (net (code "46") (name "Net-(U$63B-+IN)") (class "Default")
      (node (ref "R43") (pin "2") (pinfunction "2_2") (pintype "passive"))
      (node (ref "R44") (pin "2") (pinfunction "2_2") (pintype "passive"))
      (node (ref "U$63") (pin "5") (pinfunction "+IN_5") (pintype "input"))
    )
    (net (code "47") (name "Net-(U$63B-OUT)") (class "Default")
      (node (ref "R25") (pin "1") (pinfunction "1_1") (pintype "passive"))
      (node (ref "U$63") (pin "7") (pinfunction "OUT_7") (pintype "output"))
    )
    (net (code "48") (name "Net-(U$65A-+IN)") (class "Default")
      (node (ref "R5") (pin "2") (pinfunction "2_2") (pintype "passive"))
      (node (ref "R6") (pin "2") (pinfunction "2_2") (pintype "passive"))
      (node (ref "U$65") (pin "3") (pinfunction "+IN_3") (pintype "input"))
    )
    (net (code "49") (name "Net-(U$65A--IN)") (class "Default")
      (node (ref "R39") (pin "2") (pinfunction "2_2") (pintype "passive"))
      (node (ref "R7") (pin "1") (pinfunction "1_1") (pintype "passive"))
      (node (ref "U$65") (pin "4") (pinfunction "-IN_4") (pintype "input"))
    )
    (net (code "50") (name "Net-(U$65A-OUT)") (class "Default")
      (node (ref "R12") (pin "1") (pinfunction "1_1") (pintype "passive"))
      (node (ref "R14") (pin "1") (pinfunction "1_1") (pintype "passive"))
      (node (ref "R7") (pin "2") (pinfunction "2_2") (pintype "passive"))
      (node (ref "U$65") (pin "1") (pinfunction "OUT_1") (pintype "output"))
    )
    (net (code "51") (name "Net-(U$66A-+IN)") (class "Default")
      (node (ref "R53") (pin "1") (pinfunction "1_1") (pintype "passive"))
      (node (ref "U$66") (pin "1") (pinfunction "OUT_1") (pintype "output"))
      (node (ref "U$66") (pin "3") (pinfunction "+IN_3") (pintype "input"))
    )
    (net (code "52") (name "Net-(U$67-S)") (class "Default")
      (node (ref "C1") (pin "1") (pinfunction "1_1") (pintype "passive"))
      (node (ref "R1") (pin "2") (pinfunction "2_2") (pintype "passive"))
      (node (ref "R50") (pin "1") (pinfunction "1_1") (pintype "passive"))
      (node (ref "U$67") (pin "2") (pinfunction "S_2") (pintype "passive"))
    )
    (net (code "53") (name "Net-(U$68-S)") (class "Default")
      (node (ref "C2") (pin "1") (pinfunction "1_1") (pintype "passive"))
      (node (ref "R2") (pin "2") (pinfunction "2_2") (pintype "passive"))
      (node (ref "R49") (pin "1") (pinfunction "1_1") (pintype "passive"))
      (node (ref "U$68") (pin "2") (pinfunction "S_2") (pintype "passive"))
    )
    (net (code "54") (name "unconnected-(A/D-Pad17)") (class "Default")
      (node (ref "A/D") (pin "17") (pinfunction "17_17") (pintype "passive"))
    )
    (net (code "55") (name "unconnected-(A/D-Pad19)") (class "Default")
      (node (ref "A/D") (pin "19") (pinfunction "19_19") (pintype "passive"))
    )
    (net (code "56") (name "unconnected-(A/D-Pad21)") (class "Default")
      (node (ref "A/D") (pin "21") (pinfunction "21_21") (pintype "passive"))
    )
    (net (code "57") (name "unconnected-(SV1-Pad2)") (class "Default")
      (node (ref "SV1") (pin "2") (pinfunction "2_2") (pintype "passive"))
    )
  )
)
